# Doamsch.net
KiCad netlist of a schematic drawn in Altium Designer
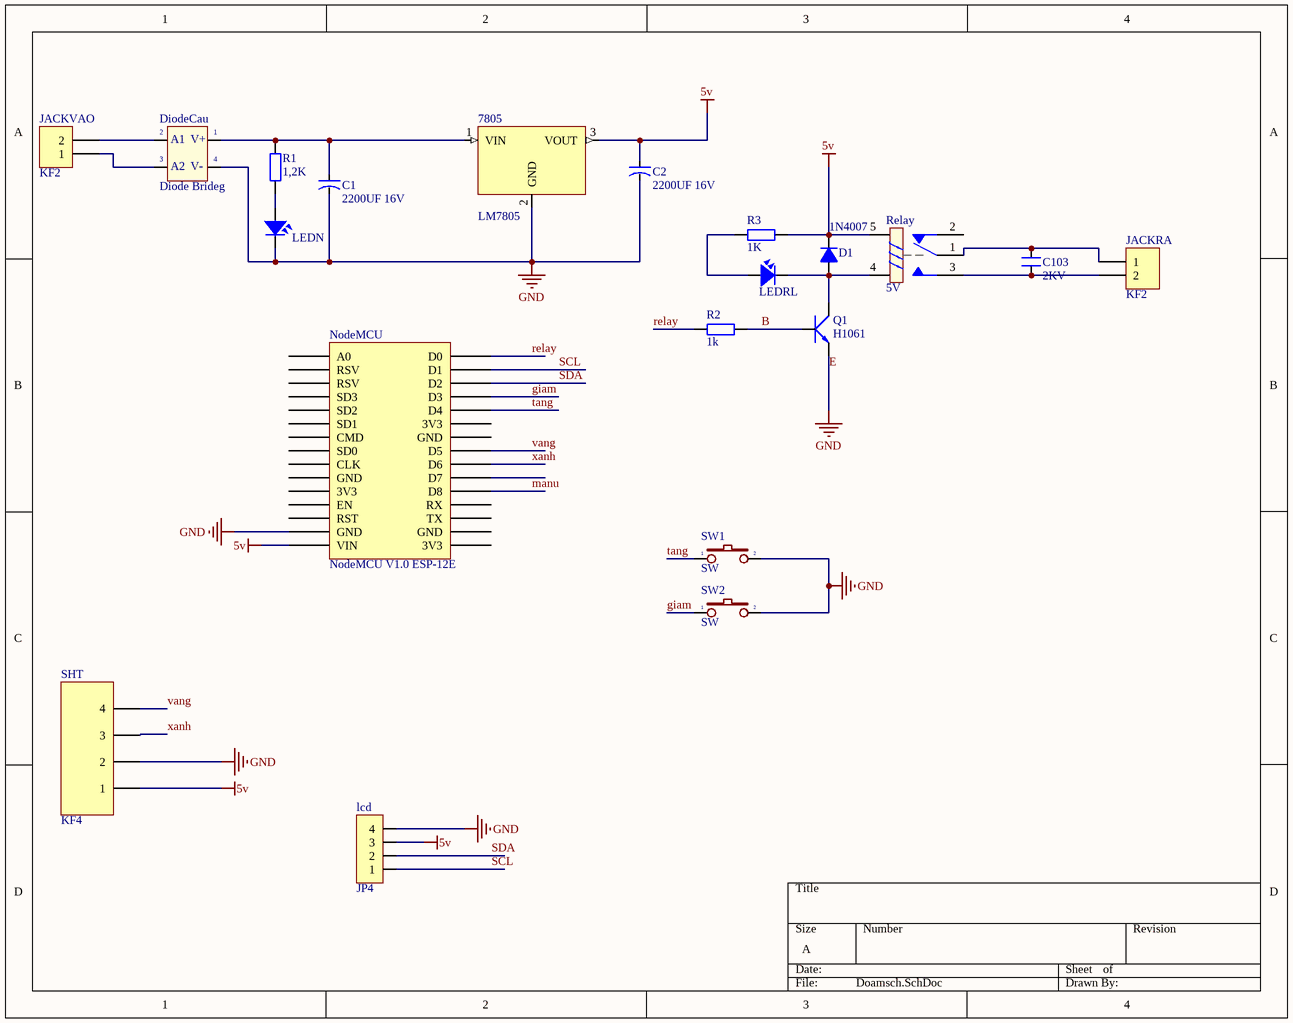
[diagram p0: Doamsch.SchDoc]

(export (version "E")
  (design (tool "Eeschema 10.0.6"))
  (components
    (comp (ref "7805")
      (value "LM7805")
      (footprint "QTO-220H3")
      (description "TO-220")
      (libsource (lib "Cty1") (part "LM7805"))
    )
    (comp (ref "C1")
      (value "2200UF 16V")
      (footprint "CA-ALU-10")
      (description "Capacitor (Semiconductor SIM Model)")
      (fields (field (name "PUBLISHER") "Altium Limited"))
      (libsource (lib "LIBRARY") (part "CN-ALU-DIP"))
    )
    (comp (ref "C2")
      (value "2200UF 16V")
      (footprint "CA-ALU-10")
      (description "Capacitor (Semiconductor SIM Model)")
      (fields (field (name "PUBLISHER") "Altium Limited"))
      (libsource (lib "LIBRARY") (part "CN-ALU-DIP"))
    )
    (comp (ref "C103") (value "2KV") (footprint "CN2.5") (libsource (lib "LIBRARY") (part "CN")))
    (comp (ref "D1")
      (value "1N4007")
      (footprint "D1A")
      (description "Diode 1A")
      (libsource (lib "Cty1") (part "D1A"))
    )
    (comp (ref "DiodeCau")
      (value "Diode Brideg")
      (footprint "DIO-Bri 5A")
      (description "Convert AC to DC voltage, 4 pin")
      (libsource (lib "LIBRARY") (part "DIODE BRIGDE"))
    )
    (comp (ref "JACKRA")
      (value "KF2")
      (footprint "KF2-5.08")
      (fields
        (field (name "MANUFACTURER") "Würth Elektronik eiSos GmbH")
        (field (name "PARTNO") "691103110002")
        (field (name "CREATED BY") "Karrer Zheng")
      )
      (libsource (lib "") (part "KF2_1"))
    )
    (comp (ref "JACKVAO")
      (value "KF2")
      (footprint "KF2-5.08")
      (fields
        (field (name "MANUFACTURER") "Würth Elektronik eiSos GmbH")
        (field (name "PARTNO") "691103110002")
        (field (name "CREATED BY") "Karrer Zheng")
      )
      (libsource (lib "LIBRARY") (part "KF2"))
    )
    (comp (ref "lcd")
      (value "JP4")
      (footprint "JP4-C1T")
      (description "WR-PHD 2.54 mm Angled Socket Header")
      (fields
        (field (name "MANUFACTURER") "Würth Elektronik eiSos GmbH")
        (field (name "PARTNO") "613004143121")
        (field (name "CREATED BY") "Karrer Zheng")
      )
      (libsource (lib "LIBRARY") (part "JP4"))
    )
    (comp (ref "LEDN")
      (value "LED")
      (footprint "LED-5-RED")
      (description "LED Single colour Green and Red")
      (libsource (lib "LIBRARY") (part "LED"))
    )
    (comp (ref "LEDRL")
      (value "LED")
      (footprint "LED-5-RED")
      (description "LED Single colour Green and Red")
      (libsource (lib "LIBRARY") (part "LED"))
    )
    (comp (ref "NodeMCU")
      (value "NodeMCU V1.0 ESP-12E")
      (footprint "NodeMCU V1.0 ESP-12E")
      (description "NodeMCU V1.0 ESP8266 (ESP-12E)")
      (libsource (lib "nodemcu") (part "NodeMCU V1.0 ESP-12E"))
    )
    (comp (ref "Q1")
      (value "H1061")
      (footprint "QTO-220")
      (description "P 1W, BCE")
      (libsource (lib "syhaunguyen") (part "NPN_BCE"))
    )
    (comp (ref "R1")
      (value "1,2K")
      (footprint "R1/4W")
      (description "Resistor 1/4W")
      (libsource (lib "Cty1") (part "R1/4W"))
    )
    (comp (ref "R2")
      (value "1k")
      (footprint "R1/4W")
      (description "Resistor 1/4W")
      (libsource (lib "Cty1") (part "R1/4W"))
    )
    (comp (ref "R3")
      (value "1K")
      (footprint "R1/4W")
      (description "Resistor 1/4W")
      (libsource (lib "Cty1") (part "R1/4W"))
    )
    (comp (ref "Relay")
      (value "5V")
      (footprint "RELAY 5")
      (description "Relay SPDT,10A - 12VDC 5 Pin")
      (libsource (lib "LIBRARY") (part "Relay 5"))
    )
    (comp (ref "SHT")
      (value "KF4")
      (footprint "KF4-5.08")
      (fields
        (field (name "MANUFACTURER") "Würth Elektronik eiSos GmbH")
        (field (name "PARTNO") "691133710004")
        (field (name "CREATED BY") "Baojun Chen")
      )
      (libsource (lib "LIBRARY") (part "KF4"))
    )
    (comp (ref "SW1")
      (value "SW")
      (footprint "SW-2P-S")
      (description "Switch button 2 pin")
      (libsource (lib "Cty1") (part "SW2"))
    )
    (comp (ref "SW2")
      (value "SW")
      (footprint "SW-2P-S")
      (description "Switch button 2 pin")
      (libsource (lib "Cty1") (part "SW2"))
    )
  )
  (nets
    (net (code "1") (name "/B") (class "Default")
      (node (ref "Q1") (pin "1") (pinfunction "B_1") (pintype "passive"))
      (node (ref "R2") (pin "2") (pinfunction "2_2") (pintype "passive"))
    )
    (net (code "2") (name "/SCL") (class "Default")
      (node (ref "NodeMCU") (pin "D1") (pinfunction "D1_D1") (pintype "passive"))
      (node (ref "lcd") (pin "1") (pinfunction "1_1") (pintype "passive"))
    )
    (net (code "3") (name "/SDA") (class "Default")
      (node (ref "NodeMCU") (pin "D2") (pinfunction "D2_D2") (pintype "passive"))
      (node (ref "lcd") (pin "2") (pinfunction "2_2") (pintype "passive"))
    )
    (net (code "4") (name "/giam") (class "Default")
      (node (ref "NodeMCU") (pin "D3") (pinfunction "D3_D3") (pintype "passive"))
      (node (ref "SW2") (pin "1") (pinfunction "1_1") (pintype "passive"))
    )
    (net (code "5") (name "/manu") (class "Default")
      (node (ref "NodeMCU") (pin "D8") (pinfunction "D8_D8") (pintype "passive"))
    )
    (net (code "6") (name "/relay") (class "Default")
      (node (ref "NodeMCU") (pin "D0") (pinfunction "D0_D0") (pintype "passive"))
      (node (ref "R2") (pin "1") (pinfunction "1_1") (pintype "passive"))
    )
    (net (code "7") (name "/tang") (class "Default")
      (node (ref "NodeMCU") (pin "D4") (pinfunction "D4_D4") (pintype "passive"))
      (node (ref "SW1") (pin "1") (pinfunction "1_1") (pintype "passive"))
    )
    (net (code "8") (name "/vang") (class "Default")
      (node (ref "NodeMCU") (pin "D5") (pinfunction "D5_D5") (pintype "passive"))
      (node (ref "SHT") (pin "4") (pinfunction "4_4") (pintype "passive"))
    )
    (net (code "9") (name "/xanh") (class "Default")
      (node (ref "NodeMCU") (pin "D6") (pinfunction "D6_D6") (pintype "passive"))
      (node (ref "SHT") (pin "3") (pinfunction "3_3") (pintype "passive"))
    )
    (net (code "10") (name "5v") (class "Default")
      (node (ref "7805") (pin "3") (pinfunction "VOUT_3") (pintype "output"))
      (node (ref "C2") (pin "1") (pinfunction "1_1") (pintype "passive"))
      (node (ref "D1") (pin "2") (pinfunction "K_2") (pintype "passive"))
      (node (ref "NodeMCU") (pin "VIN") (pinfunction "VIN_VIN") (pintype "passive"))
      (node (ref "R3") (pin "2") (pinfunction "2_2") (pintype "passive"))
      (node (ref "Relay") (pin "5") (pinfunction "5_5") (pintype "passive"))
      (node (ref "SHT") (pin "1") (pinfunction "1_1") (pintype "passive"))
      (node (ref "lcd") (pin "3") (pinfunction "3_3") (pintype "passive"))
    )
    (net (code "11") (name "GND") (class "Default")
      (node (ref "7805") (pin "2") (pinfunction "GND_2") (pintype "power_in"))
      (node (ref "C1") (pin "2") (pinfunction "2_2") (pintype "passive"))
      (node (ref "C2") (pin "2") (pinfunction "2_2") (pintype "passive"))
      (node (ref "DiodeCau") (pin "4") (pinfunction "-V_OUT_4") (pintype "passive"))
      (node (ref "LEDN") (pin "2") (pinfunction "2_2") (pintype "passive"))
      (node (ref "NodeMCU") (pin "GND") (pinfunction "GND_GND") (pintype "passive"))
      (node (ref "Q1") (pin "3") (pinfunction "E_3") (pintype "passive"))
      (node (ref "SHT") (pin "2") (pinfunction "2_2") (pintype "passive"))
      (node (ref "SW1") (pin "2") (pinfunction "2_2") (pintype "passive"))
      (node (ref "SW2") (pin "2") (pinfunction "2_2") (pintype "passive"))
      (node (ref "lcd") (pin "4") (pinfunction "4_4") (pintype "passive"))
    )
    (net (code "12") (name "Net-(7805-VIN)") (class "Default")
      (node (ref "7805") (pin "1") (pinfunction "VIN_1") (pintype "input"))
      (node (ref "C1") (pin "1") (pinfunction "1_1") (pintype "passive"))
      (node (ref "DiodeCau") (pin "1") (pinfunction "+V_OUT_1") (pintype "passive"))
      (node (ref "R1") (pin "2") (pinfunction "2_2") (pintype "passive"))
    )
    (net (code "13") (name "Net-(C103-Pad1)") (class "Default")
      (node (ref "C103") (pin "1") (pinfunction "1_1") (pintype "passive"))
      (node (ref "JACKRA") (pin "2") (pinfunction "2_2") (pintype "passive"))
      (node (ref "Relay") (pin "3") (pinfunction "3_3") (pintype "passive"))
    )
    (net (code "14") (name "Net-(C103-Pad2)") (class "Default")
      (node (ref "C103") (pin "2") (pinfunction "2_2") (pintype "passive"))
      (node (ref "JACKRA") (pin "1") (pinfunction "1_1") (pintype "passive"))
      (node (ref "Relay") (pin "1") (pinfunction "1_1") (pintype "passive"))
    )
    (net (code "15") (name "Net-(D1-A)") (class "Default")
      (node (ref "D1") (pin "1") (pinfunction "A_1") (pintype "passive"))
      (node (ref "LEDRL") (pin "2") (pinfunction "2_2") (pintype "passive"))
      (node (ref "Q1") (pin "2") (pinfunction "C_2") (pintype "passive"))
      (node (ref "Relay") (pin "4") (pinfunction "4_4") (pintype "passive"))
    )
    (net (code "16") (name "Net-(DiodeCau-AC1)") (class "Default")
      (node (ref "DiodeCau") (pin "2") (pinfunction "AC1_2") (pintype "passive"))
      (node (ref "JACKVAO") (pin "2") (pinfunction "2_2") (pintype "passive"))
    )
    (net (code "17") (name "Net-(DiodeCau-AC2)") (class "Default")
      (node (ref "DiodeCau") (pin "3") (pinfunction "AC2_3") (pintype "passive"))
      (node (ref "JACKVAO") (pin "1") (pinfunction "1_1") (pintype "passive"))
    )
    (net (code "18") (name "Net-(LEDN-Pad1)") (class "Default")
      (node (ref "LEDN") (pin "1") (pinfunction "1_1") (pintype "passive"))
      (node (ref "R1") (pin "1") (pinfunction "1_1") (pintype "passive"))
    )
    (net (code "19") (name "Net-(LEDRL-Pad1)") (class "Default")
      (node (ref "LEDRL") (pin "1") (pinfunction "1_1") (pintype "passive"))
      (node (ref "R3") (pin "1") (pinfunction "1_1") (pintype "passive"))
    )
    (net (code "20") (name "unconnected-(NodeMCU-Pad3V3)") (class "Default")
      (node (ref "NodeMCU") (pin "3V3") (pinfunction "3V3_3V3") (pintype "passive"))
    )
    (net (code "21") (name "unconnected-(NodeMCU-Pad3V3)_1") (class "Default")
      (node (ref "NodeMCU") (pin "3V3") (pinfunction "3V3_3V3") (pintype "passive"))
    )
    (net (code "22") (name "unconnected-(NodeMCU-Pad3V3)_2") (class "Default")
      (node (ref "NodeMCU") (pin "3V3") (pinfunction "3V3_3V3") (pintype "passive"))
    )
    (net (code "23") (name "unconnected-(NodeMCU-PadA0)") (class "Default")
      (node (ref "NodeMCU") (pin "A0") (pinfunction "A0_A0") (pintype "passive"))
    )
    (net (code "24") (name "unconnected-(NodeMCU-PadCLK)") (class "Default")
      (node (ref "NodeMCU") (pin "CLK") (pinfunction "CLK_CLK") (pintype "passive"))
    )
    (net (code "25") (name "unconnected-(NodeMCU-PadCMD)") (class "Default")
      (node (ref "NodeMCU") (pin "CMD") (pinfunction "CMD_CMD") (pintype "passive"))
    )
    (net (code "26") (name "unconnected-(NodeMCU-PadD7)") (class "Default")
      (node (ref "NodeMCU") (pin "D7") (pinfunction "D7_D7") (pintype "passive"))
    )
    (net (code "27") (name "unconnected-(NodeMCU-PadEN)") (class "Default")
      (node (ref "NodeMCU") (pin "EN") (pinfunction "EN_EN") (pintype "passive"))
    )
    (net (code "28") (name "unconnected-(NodeMCU-PadGND)") (class "Default")
      (node (ref "NodeMCU") (pin "GND") (pinfunction "GND_GND") (pintype "passive"))
    )
    (net (code "29") (name "unconnected-(NodeMCU-PadGND)_1") (class "Default")
      (node (ref "NodeMCU") (pin "GND") (pinfunction "GND_GND") (pintype "passive"))
    )
    (net (code "30") (name "unconnected-(NodeMCU-PadGND)_2") (class "Default")
      (node (ref "NodeMCU") (pin "GND") (pinfunction "GND_GND") (pintype "passive"))
    )
    (net (code "31") (name "unconnected-(NodeMCU-PadRST)") (class "Default")
      (node (ref "NodeMCU") (pin "RST") (pinfunction "RST_RST") (pintype "passive"))
    )
    (net (code "32") (name "unconnected-(NodeMCU-PadRSV)") (class "Default")
      (node (ref "NodeMCU") (pin "RSV") (pinfunction "RSV_RSV") (pintype "passive"))
    )
    (net (code "33") (name "unconnected-(NodeMCU-PadRSV)_1") (class "Default")
      (node (ref "NodeMCU") (pin "RSV") (pinfunction "RSV_RSV") (pintype "passive"))
    )
    (net (code "34") (name "unconnected-(NodeMCU-PadRX)") (class "Default")
      (node (ref "NodeMCU") (pin "RX") (pinfunction "RX_RX") (pintype "passive"))
    )
    (net (code "35") (name "unconnected-(NodeMCU-PadSD0)") (class "Default")
      (node (ref "NodeMCU") (pin "SD0") (pinfunction "SD0_SD0") (pintype "passive"))
    )
    (net (code "36") (name "unconnected-(NodeMCU-PadSD1)") (class "Default")
      (node (ref "NodeMCU") (pin "SD1") (pinfunction "SD1_SD1") (pintype "passive"))
    )
    (net (code "37") (name "unconnected-(NodeMCU-PadSD2)") (class "Default")
      (node (ref "NodeMCU") (pin "SD2") (pinfunction "SD2_SD2") (pintype "passive"))
    )
    (net (code "38") (name "unconnected-(NodeMCU-PadSD3)") (class "Default")
      (node (ref "NodeMCU") (pin "SD3") (pinfunction "SD3_SD3") (pintype "passive"))
    )
    (net (code "39") (name "unconnected-(NodeMCU-PadTX)") (class "Default")
      (node (ref "NodeMCU") (pin "TX") (pinfunction "TX_TX") (pintype "passive"))
    )
    (net (code "40") (name "unconnected-(Relay-Pad2)") (class "Default")
      (node (ref "Relay") (pin "2") (pinfunction "2_2") (pintype "passive"))
    )
  )
)
